# PrototypeBoardV1A.net
KiCad netlist of a schematic drawn in EasyEDA Pro
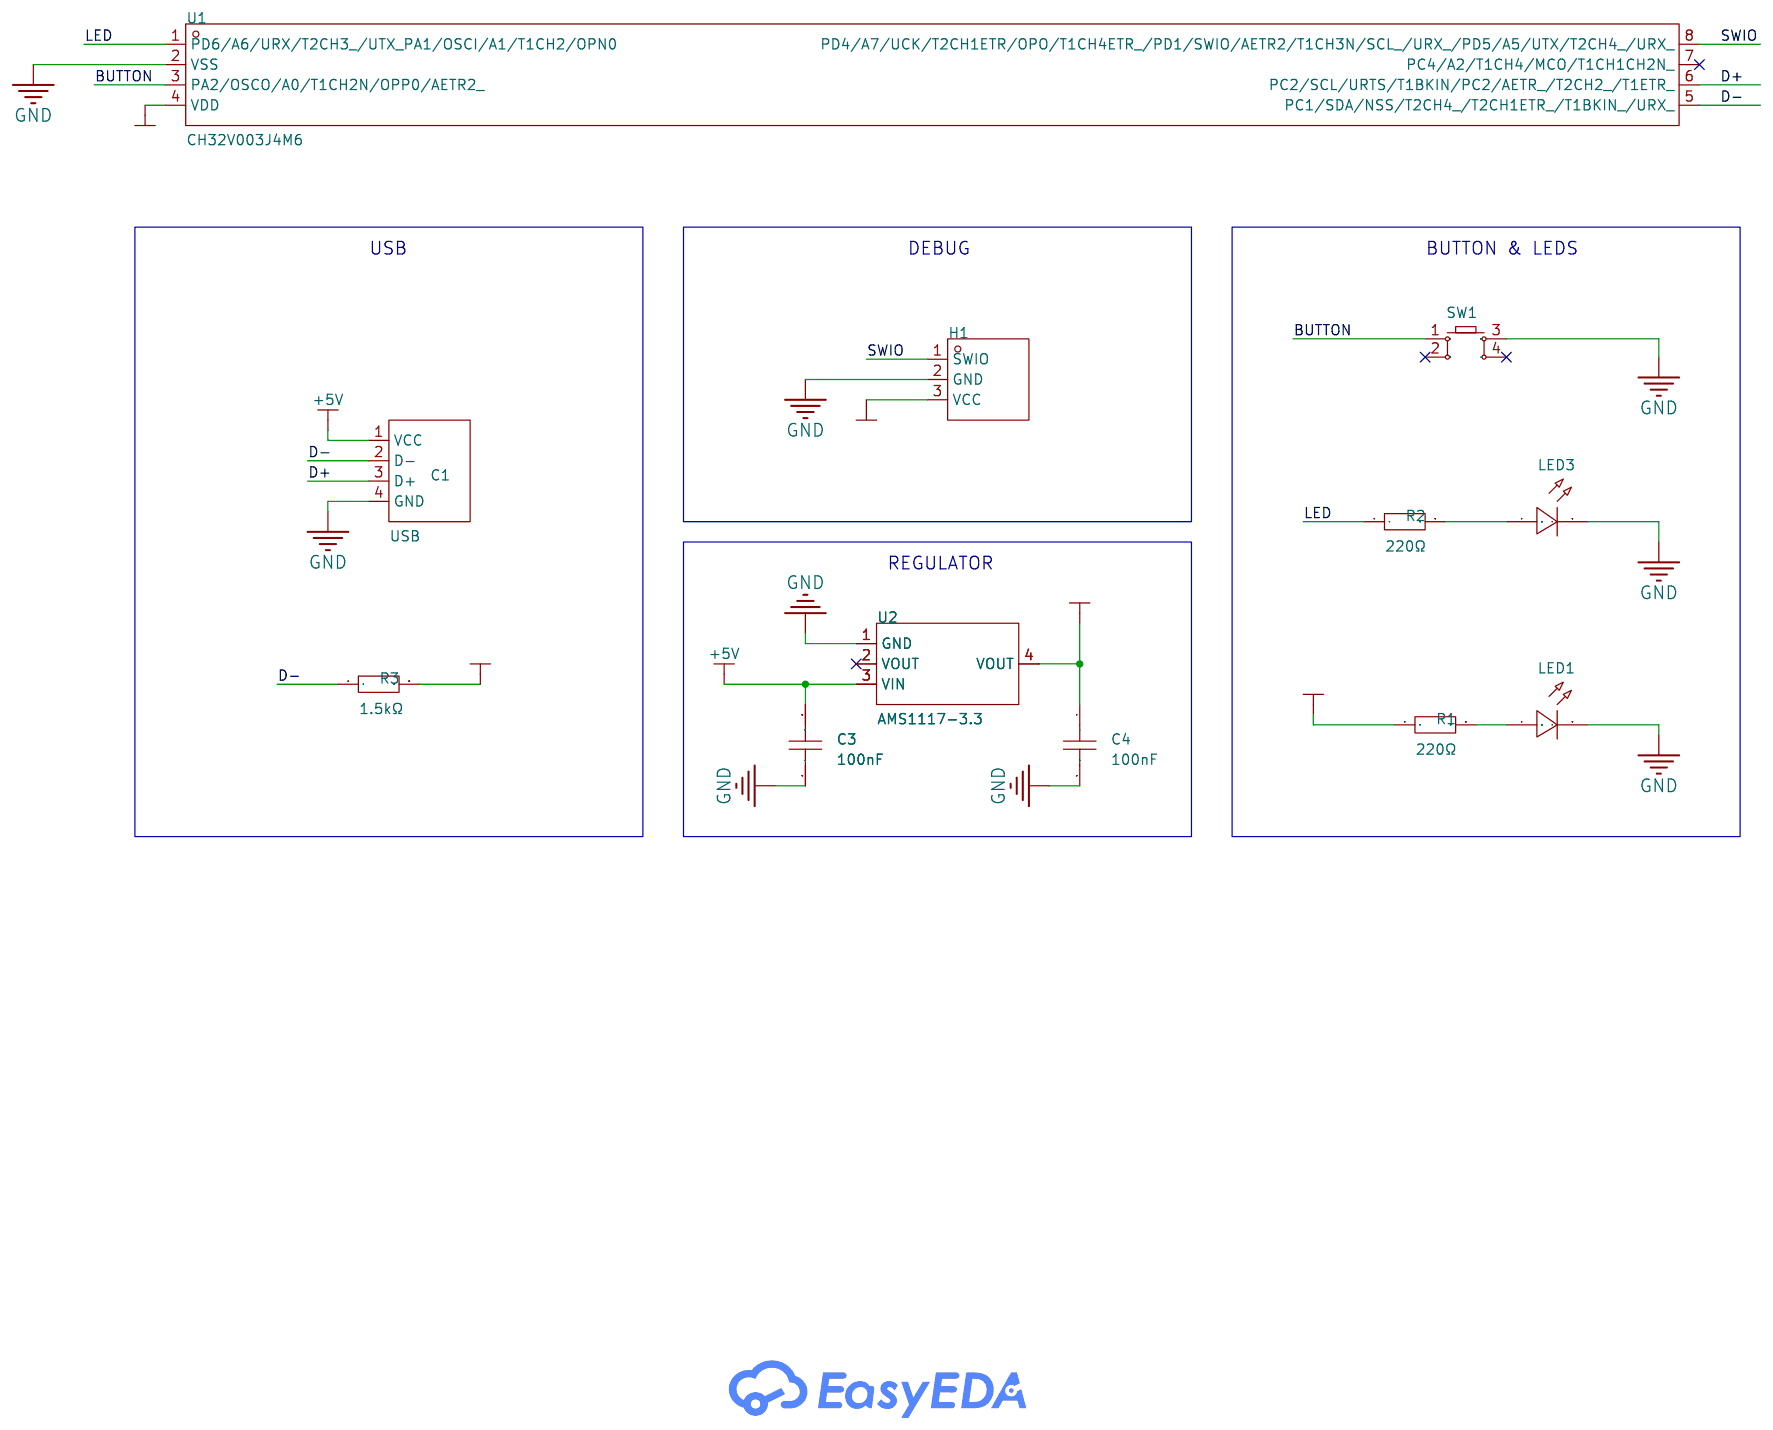
[diagram p0: schematic sheet]

(export (version "E")
  (design (tool "Eeschema 10.0.6"))
  (components
    (comp (ref "C1")
      (value "USB")
      (footprint "easyedapro:USB Type-C 4P")
      (libsource (lib "easyedapro") (part "USB Type-C 4P Board"))
    )
    (comp (ref "C3")
      (value "100nF")
      (footprint "easyedapro:CAP-TH_L5.8-W3.0-P4.7-D0.45")
      (fields (field (name "Manufacturer Part") "1C10Z5U104M050B") (field (name "Manufacturer") "VISHAY(威世)"))
      (libsource (lib "easyedapro") (part "1C10Z5U104M050B"))
    )
    (comp (ref "C4")
      (value "100nF")
      (footprint "easyedapro:CAP-TH_L5.8-W3.0-P4.7-D0.45")
      (fields (field (name "Manufacturer Part") "1C10Z5U104M050B") (field (name "Manufacturer") "VISHAY(威世)"))
      (libsource (lib "easyedapro") (part "1C10Z5U104M050B"))
    )
    (comp (ref "H1")
      (value "~")
      (footprint "easyedapro:HDR-TH_3P-P2.54-V-M")
      (libsource (lib "easyedapro") (part "PZ254V-11-03P_C2937625"))
    )
    (comp (ref "LED1")
      (value "~")
      (footprint "easyedapro:LED-TH_BD3.0-P2.54-FD")
      (libsource (lib "easyedapro") (part "LED_TH-R"))
    )
    (comp (ref "LED3")
      (value "~")
      (footprint "easyedapro:LED-TH_BD5.0-P2.54-L-RD_WHITE")
      (libsource (lib "easyedapro") (part "LED_TH-B"))
    )
    (comp (ref "R1")
      (value "220Ω")
      (footprint "easyedapro:RES-TH_BD1.8-L3.2-P7.20-D0.4")
      (libsource (lib "easyedapro") (part "Res"))
    )
    (comp (ref "R2")
      (value "220Ω")
      (footprint "easyedapro:RES-TH_BD1.8-L3.2-P7.20-D0.4")
      (libsource (lib "easyedapro") (part "Res"))
    )
    (comp (ref "R3")
      (value "1.5kΩ")
      (footprint "easyedapro:RES-TH_BD1.8-L3.2-P7.20-D0.4")
      (libsource (lib "easyedapro") (part "Res"))
    )
    (comp (ref "SW1")
      (value "~")
      (footprint "easyedapro:KEY-TH_4P-L6.0-W6.0-P3.90-LS6.5")
      (libsource (lib "easyedapro") (part "轻触按键"))
    )
    (comp (ref "U1")
      (value "CH32V003J4M6")
      (footprint "easyedapro:SOP-8_L4.9-W3.8-P1.27-LS6.0-BL")
      (fields (field (name "Manufacturer") "WCH(南京沁恒)"))
      (libsource (lib "easyedapro") (part "CH32V003J4M6_C5346354"))
    )
    (comp (ref "U2")
      (value "AMS1117-3.3")
      (footprint "easyedapro:SOT-223-3_L6.5-W3.4-P2.30-LS7.0-BR")
      (fields (field (name "Manufacturer") "AMS"))
      (libsource (lib "easyedapro") (part "AMS1117-3.3"))
    )
  )
  (nets
    (net (code "1") (name "+3.3V") (class "Default")
      (node (ref "C4") (pin "1") (pinfunction "1_1") (pintype "unspecified"))
      (node (ref "H1") (pin "3") (pinfunction "VCC_3") (pintype "unspecified"))
      (node (ref "R1") (pin "1") (pinfunction "1_1") (pintype "input"))
      (node (ref "R3") (pin "2") (pinfunction "2_2") (pintype "input"))
      (node (ref "U1") (pin "4") (pinfunction "VDD_4") (pintype "unspecified"))
      (node (ref "U2") (pin "4") (pinfunction "VOUT_4") (pintype "unspecified"))
    )
    (net (code "2") (name "+5V") (class "Default")
      (node (ref "C1") (pin "1") (pinfunction "VCC_1") (pintype "input"))
      (node (ref "C3") (pin "2") (pinfunction "2_2") (pintype "unspecified"))
      (node (ref "U2") (pin "3") (pinfunction "VIN_3") (pintype "unspecified"))
    )
    (net (code "3") (name "/BUTTON") (class "Default")
      (node (ref "SW1") (pin "1") (pinfunction "1_1") (pintype "input"))
      (node (ref "U1") (pin "3") (pinfunction "PA2/OSCO/A0/T1CH2N/OPP0/AETR2__3") (pintype "unspecified"))
    )
    (net (code "4") (name "/D+") (class "Default")
      (node (ref "C1") (pin "3") (pinfunction "D+_3") (pintype "input"))
      (node (ref "U1") (pin "6") (pinfunction "PC2/SCL/URTS/T1BKIN/PC2/AETR_/T2CH2_/T1ETR__6") (pintype "unspecified"))
    )
    (net (code "5") (name "/D-") (class "Default")
      (node (ref "C1") (pin "2") (pinfunction "D-_2") (pintype "input"))
      (node (ref "R3") (pin "1") (pinfunction "1_1") (pintype "input"))
      (node (ref "U1") (pin "5") (pinfunction "PC1/SDA/NSS/T2CH4_/T2CH1ETR_/T1BKIN_/URX__5") (pintype "unspecified"))
    )
    (net (code "6") (name "/LED") (class "Default")
      (node (ref "R2") (pin "1") (pinfunction "1_1") (pintype "input"))
      (node (ref "U1") (pin "1") (pinfunction "PD6/A6/URX/T2CH3_/UTX_PA1/OSCI/A1/T1CH2/OPN0_1") (pintype "unspecified"))
    )
    (net (code "7") (name "/SWIO") (class "Default")
      (node (ref "H1") (pin "1") (pinfunction "SWIO_1") (pintype "unspecified"))
      (node (ref "U1") (pin "8") (pinfunction "PD4/A7/UCK/T2CH1ETR/OPO/T1CH4ETR_/PD1/SWIO/AETR2/T1CH3N/SCL_/URX_/PD5/A5/UTX/T2CH4_/URX__8") (pintype "unspecified"))
    )
    (net (code "8") (name "GND") (class "Default")
      (node (ref "C1") (pin "4") (pinfunction "GND_4") (pintype "input"))
      (node (ref "C3") (pin "1") (pinfunction "1_1") (pintype "unspecified"))
      (node (ref "C4") (pin "2") (pinfunction "2_2") (pintype "unspecified"))
      (node (ref "H1") (pin "2") (pinfunction "GND_2") (pintype "unspecified"))
      (node (ref "LED1") (pin "2") (pinfunction "A_2") (pintype "input"))
      (node (ref "LED3") (pin "2") (pinfunction "A_2") (pintype "input"))
      (node (ref "SW1") (pin "3") (pinfunction "3_3") (pintype "input"))
      (node (ref "U1") (pin "2") (pinfunction "VSS_2") (pintype "unspecified"))
      (node (ref "U2") (pin "1") (pinfunction "GND_1") (pintype "unspecified"))
    )
    (net (code "9") (name "Net-(LED1-C)") (class "Default")
      (node (ref "LED1") (pin "1") (pinfunction "C_1") (pintype "input"))
      (node (ref "R1") (pin "2") (pinfunction "2_2") (pintype "input"))
    )
    (net (code "10") (name "Net-(LED3-C)") (class "Default")
      (node (ref "LED3") (pin "1") (pinfunction "C_1") (pintype "input"))
      (node (ref "R2") (pin "2") (pinfunction "2_2") (pintype "input"))
    )
    (net (code "11") (name "unconnected-(SW1-Pad2)") (class "Default")
      (node (ref "SW1") (pin "2") (pinfunction "2_2") (pintype "input+no_connect"))
    )
    (net (code "12") (name "unconnected-(SW1-Pad4)") (class "Default")
      (node (ref "SW1") (pin "4") (pinfunction "4_4") (pintype "input+no_connect"))
    )
    (net (code "13") (name "unconnected-(U1-PC4{slash}A2{slash}T1CH4{slash}MCO{slash}T1CH1CH2N_-Pad7)") (class "Default")
      (node (ref "U1") (pin "7") (pinfunction "PC4/A2/T1CH4/MCO/T1CH1CH2N__7") (pintype "unspecified+no_connect"))
    )
    (net (code "14") (name "unconnected-(U2-VOUT-Pad2)") (class "Default")
      (node (ref "U2") (pin "2") (pinfunction "VOUT_2") (pintype "unspecified+no_connect"))
    )
  )
)
